# Galaksija_keyboard_adapter.net
KiCad netlist of a schematic drawn in EAGLE
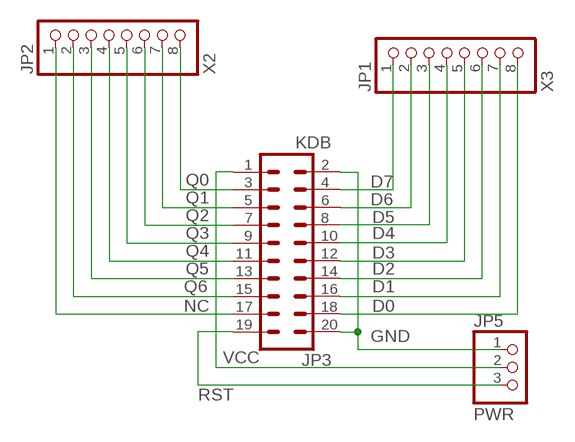
[diagram p0: schematic, sheet 1]

(export (version "E")
  (design (tool "Eeschema 10.0.6"))
  (components
    (comp (ref "JP1")
      (value "X3")
      (footprint "eagle-import:1X08")
      (libsource (lib "eagle-import") (part "PINHD-1X8"))
    )
    (comp (ref "JP2")
      (value "X2")
      (footprint "eagle-import:1X08")
      (libsource (lib "eagle-import") (part "PINHD-1X8"))
    )
    (comp (ref "JP3")
      (value "KDB")
      (footprint "eagle-import:ML20")
      (libsource (lib "eagle-import") (part "ML20"))
    )
    (comp (ref "JP5")
      (value "PWR")
      (footprint "eagle-import:1X03")
      (libsource (lib "eagle-import") (part "PINHD-1X3"))
    )
  )
  (nets
    (net (code "1") (name "/D0") (class "Default")
      (node (ref "JP1") (pin "8") (pinfunction "8_8") (pintype "passive"))
      (node (ref "JP3") (pin "18") (pinfunction "18_18") (pintype "passive"))
    )
    (net (code "2") (name "/D1") (class "Default")
      (node (ref "JP1") (pin "7") (pinfunction "7_7") (pintype "passive"))
      (node (ref "JP3") (pin "16") (pinfunction "16_16") (pintype "passive"))
    )
    (net (code "3") (name "/D2") (class "Default")
      (node (ref "JP1") (pin "6") (pinfunction "6_6") (pintype "passive"))
      (node (ref "JP3") (pin "14") (pinfunction "14_14") (pintype "passive"))
    )
    (net (code "4") (name "/D3") (class "Default")
      (node (ref "JP1") (pin "5") (pinfunction "5_5") (pintype "passive"))
      (node (ref "JP3") (pin "12") (pinfunction "12_12") (pintype "passive"))
    )
    (net (code "5") (name "/D4") (class "Default")
      (node (ref "JP1") (pin "4") (pinfunction "4_4") (pintype "passive"))
      (node (ref "JP3") (pin "10") (pinfunction "10_10") (pintype "passive"))
    )
    (net (code "6") (name "/D5") (class "Default")
      (node (ref "JP1") (pin "3") (pinfunction "3_3") (pintype "passive"))
      (node (ref "JP3") (pin "8") (pinfunction "8_8") (pintype "passive"))
    )
    (net (code "7") (name "/D6") (class "Default")
      (node (ref "JP1") (pin "2") (pinfunction "2_2") (pintype "passive"))
      (node (ref "JP3") (pin "6") (pinfunction "6_6") (pintype "passive"))
    )
    (net (code "8") (name "/D7") (class "Default")
      (node (ref "JP1") (pin "1") (pinfunction "1_1") (pintype "passive"))
      (node (ref "JP3") (pin "4") (pinfunction "4_4") (pintype "passive"))
    )
    (net (code "9") (name "/GND") (class "Default")
      (node (ref "JP3") (pin "2") (pinfunction "2_2") (pintype "passive"))
      (node (ref "JP3") (pin "20") (pinfunction "20_20") (pintype "passive"))
      (node (ref "JP5") (pin "1") (pinfunction "1_1") (pintype "passive"))
    )
    (net (code "10") (name "/NC") (class "Default")
      (node (ref "JP2") (pin "1") (pinfunction "1_1") (pintype "passive"))
      (node (ref "JP3") (pin "17") (pinfunction "17_17") (pintype "passive"))
    )
    (net (code "11") (name "/Q0") (class "Default")
      (node (ref "JP2") (pin "8") (pinfunction "8_8") (pintype "passive"))
      (node (ref "JP3") (pin "3") (pinfunction "3_3") (pintype "passive"))
    )
    (net (code "12") (name "/Q1") (class "Default")
      (node (ref "JP2") (pin "7") (pinfunction "7_7") (pintype "passive"))
      (node (ref "JP3") (pin "5") (pinfunction "5_5") (pintype "passive"))
    )
    (net (code "13") (name "/Q2") (class "Default")
      (node (ref "JP2") (pin "6") (pinfunction "6_6") (pintype "passive"))
      (node (ref "JP3") (pin "7") (pinfunction "7_7") (pintype "passive"))
    )
    (net (code "14") (name "/Q3") (class "Default")
      (node (ref "JP2") (pin "5") (pinfunction "5_5") (pintype "passive"))
      (node (ref "JP3") (pin "9") (pinfunction "9_9") (pintype "passive"))
    )
    (net (code "15") (name "/Q4") (class "Default")
      (node (ref "JP2") (pin "4") (pinfunction "4_4") (pintype "passive"))
      (node (ref "JP3") (pin "11") (pinfunction "11_11") (pintype "passive"))
    )
    (net (code "16") (name "/Q5") (class "Default")
      (node (ref "JP2") (pin "3") (pinfunction "3_3") (pintype "passive"))
      (node (ref "JP3") (pin "13") (pinfunction "13_13") (pintype "passive"))
    )
    (net (code "17") (name "/Q6") (class "Default")
      (node (ref "JP2") (pin "2") (pinfunction "2_2") (pintype "passive"))
      (node (ref "JP3") (pin "15") (pinfunction "15_15") (pintype "passive"))
    )
    (net (code "18") (name "/RST") (class "Default")
      (node (ref "JP3") (pin "19") (pinfunction "19_19") (pintype "passive"))
      (node (ref "JP5") (pin "3") (pinfunction "3_3") (pintype "passive"))
    )
    (net (code "19") (name "/VCC") (class "Default")
      (node (ref "JP3") (pin "1") (pinfunction "1_1") (pintype "passive"))
      (node (ref "JP5") (pin "2") (pinfunction "2_2") (pintype "passive"))
    )
  )
)
